# PlusCartUnified_X7.net
KiCad netlist of a schematic drawn in EAGLE
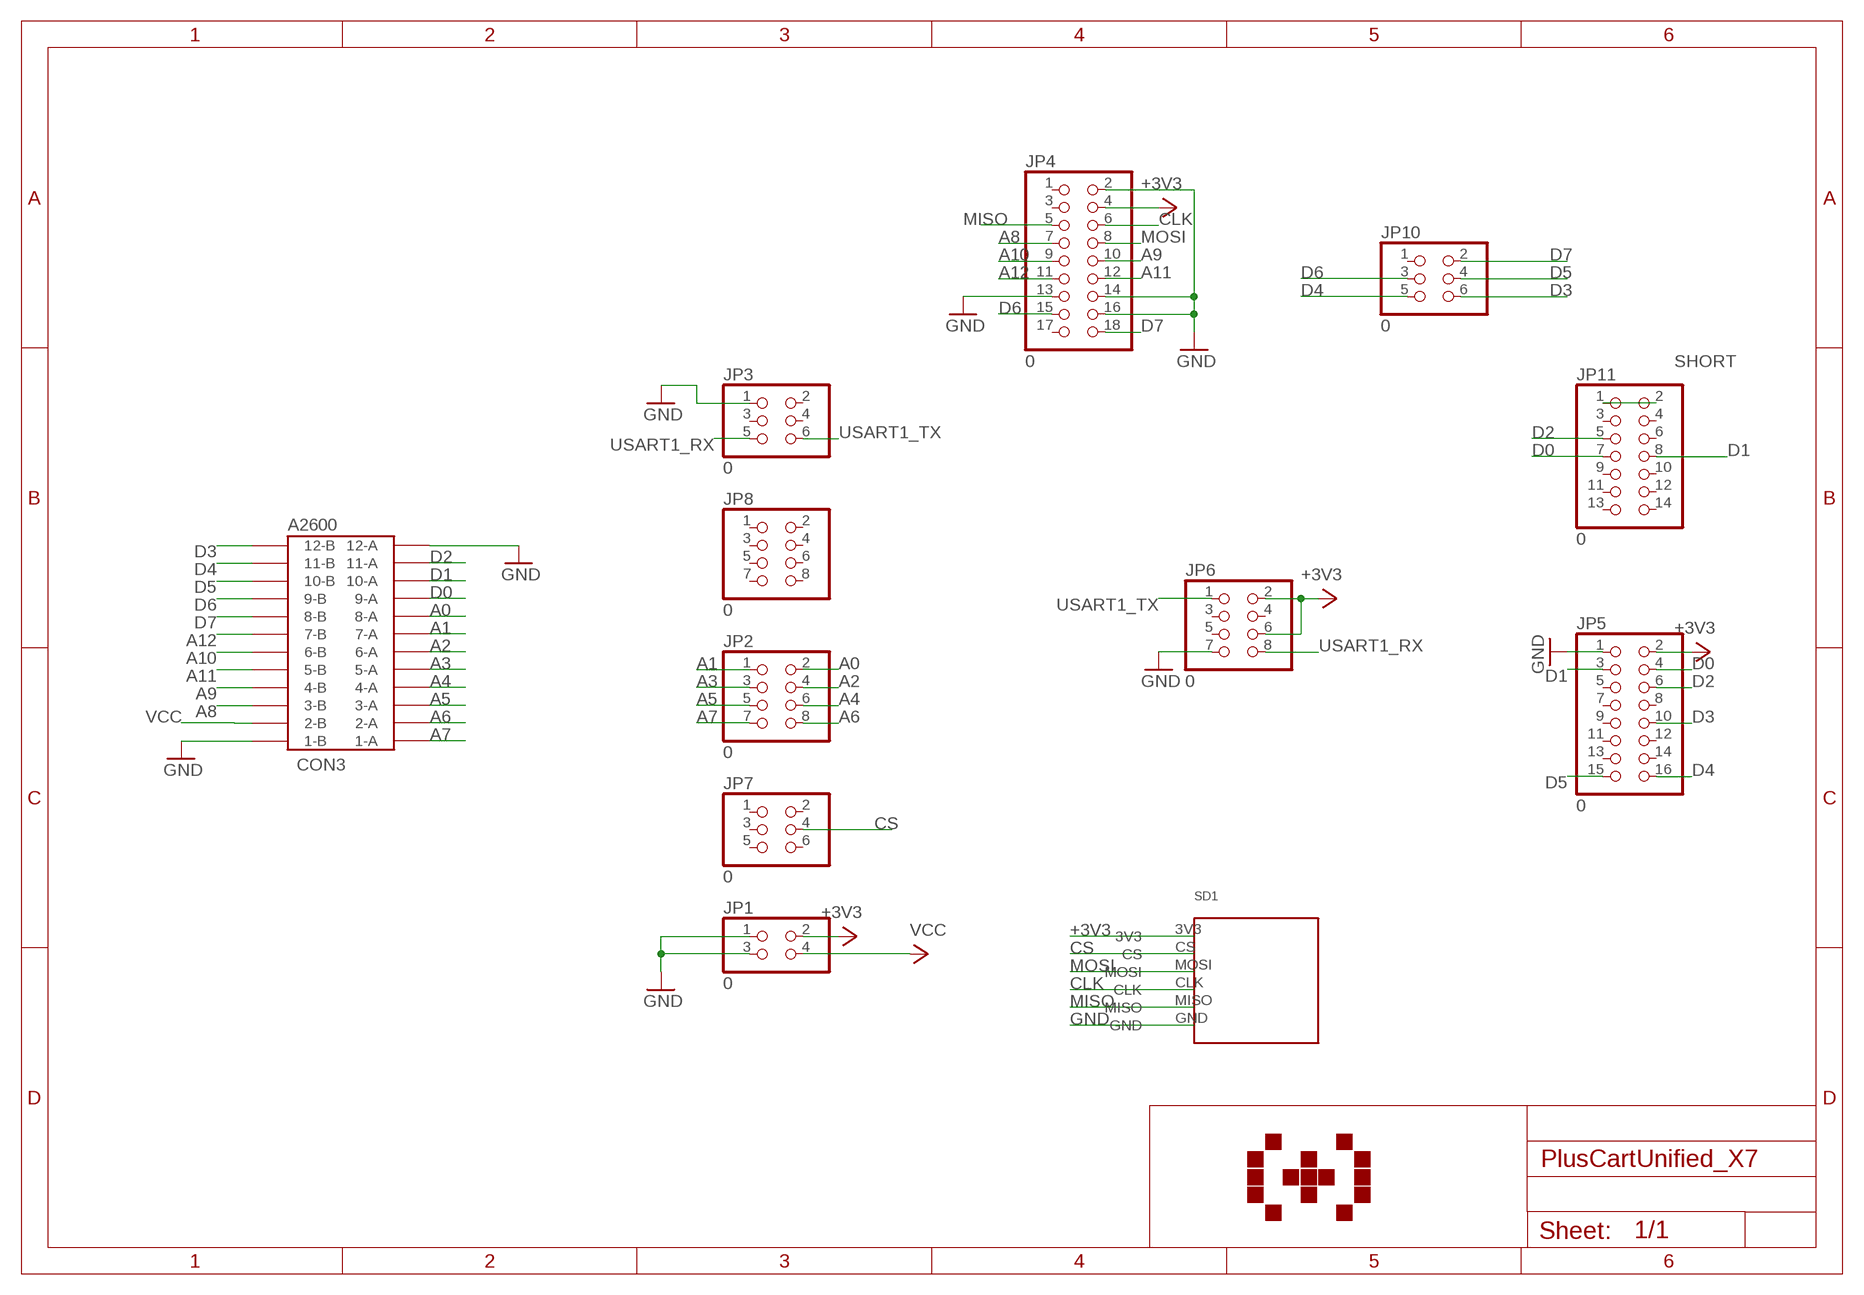
[diagram p0: schematic, sheet 1]

(export (version "E")
  (design (tool "Eeschema 10.0.6"))
  (components
    (comp (ref "CON3")
      (value "A2600")
      (footprint "eagle-import:24PINEDGE-254MM")
      (libsource (lib "eagle-import") (part "24PINEDGE-254MM"))
    )
    (comp (ref "JP1")
      (value "0")
      (footprint "eagle-import:2X02")
      (libsource (lib "eagle-import") (part "PINHD-2X2"))
    )
    (comp (ref "JP2")
      (value "0")
      (footprint "eagle-import:2X04")
      (libsource (lib "eagle-import") (part "PINHD-2X4"))
    )
    (comp (ref "JP3")
      (value "0")
      (footprint "eagle-import:2X03")
      (libsource (lib "eagle-import") (part "PINHD-2X3"))
    )
    (comp (ref "JP4")
      (value "0")
      (footprint "eagle-import:2X09")
      (libsource (lib "eagle-import") (part "PINHD-2X9"))
    )
    (comp (ref "JP5")
      (value "0")
      (footprint "eagle-import:2X08")
      (libsource (lib "eagle-import") (part "PINHD-2X8"))
    )
    (comp (ref "JP6")
      (value "0")
      (footprint "eagle-import:2X04")
      (libsource (lib "eagle-import") (part "PINHD-2X4"))
    )
    (comp (ref "JP7")
      (value "0")
      (footprint "eagle-import:2X03")
      (libsource (lib "eagle-import") (part "pinhead@1_PINHD-2X3"))
    )
    (comp (ref "JP8")
      (value "0")
      (footprint "eagle-import:2X04")
      (libsource (lib "eagle-import") (part "pinhead@1_PINHD-2X4"))
    )
    (comp (ref "JP10")
      (value "0")
      (footprint "eagle-import:2X03")
      (libsource (lib "eagle-import") (part "pinhead@1_PINHD-2X3"))
    )
    (comp (ref "JP11")
      (value "0")
      (footprint "eagle-import:2X07")
      (libsource (lib "eagle-import") (part "PINHD-2X7"))
    )
    (comp (ref "SD1")
      (value "MICROSDMICROSD2")
      (footprint "eagle-import:MICROSD_FOOTPRINT")
      (libsource (lib "eagle-import") (part "MICROSDMICROSD2"))
    )
  )
  (nets
    (net (code "1") (name "+3V3") (class "Default")
      (node (ref "JP1") (pin "2") (pinfunction "2_2") (pintype "passive"))
      (node (ref "JP4") (pin "4") (pinfunction "4_4") (pintype "passive"))
      (node (ref "JP5") (pin "2") (pinfunction "2_2") (pintype "passive"))
      (node (ref "JP6") (pin "2") (pinfunction "2_2") (pintype "passive"))
      (node (ref "JP6") (pin "6") (pinfunction "6_6") (pintype "passive"))
      (node (ref "SD1") (pin "3V3") (pinfunction "3V3_3V3") (pintype "bidirectional"))
    )
    (net (code "2") (name "/A0") (class "Default")
      (node (ref "CON3") (pin "8-A") (pinfunction "8-A_8-A") (pintype "passive"))
      (node (ref "JP2") (pin "2") (pinfunction "2_2") (pintype "passive"))
    )
    (net (code "3") (name "/A1") (class "Default")
      (node (ref "CON3") (pin "7-A") (pinfunction "7-A_7-A") (pintype "passive"))
      (node (ref "JP2") (pin "1") (pinfunction "1_1") (pintype "passive"))
    )
    (net (code "4") (name "/A2") (class "Default")
      (node (ref "CON3") (pin "6-A") (pinfunction "6-A_6-A") (pintype "passive"))
      (node (ref "JP2") (pin "4") (pinfunction "4_4") (pintype "passive"))
    )
    (net (code "5") (name "/A3") (class "Default")
      (node (ref "CON3") (pin "5-A") (pinfunction "5-A_5-A") (pintype "passive"))
      (node (ref "JP2") (pin "3") (pinfunction "3_3") (pintype "passive"))
    )
    (net (code "6") (name "/A4") (class "Default")
      (node (ref "CON3") (pin "4-A") (pinfunction "4-A_4-A") (pintype "passive"))
      (node (ref "JP2") (pin "6") (pinfunction "6_6") (pintype "passive"))
    )
    (net (code "7") (name "/A5") (class "Default")
      (node (ref "CON3") (pin "3-A") (pinfunction "3-A_3-A") (pintype "passive"))
      (node (ref "JP2") (pin "5") (pinfunction "5_5") (pintype "passive"))
    )
    (net (code "8") (name "/A6") (class "Default")
      (node (ref "CON3") (pin "2-A") (pinfunction "2-A_2-A") (pintype "passive"))
      (node (ref "JP2") (pin "8") (pinfunction "8_8") (pintype "passive"))
    )
    (net (code "9") (name "/A7") (class "Default")
      (node (ref "CON3") (pin "1-A") (pinfunction "1-A_1-A") (pintype "passive"))
      (node (ref "JP2") (pin "7") (pinfunction "7_7") (pintype "passive"))
    )
    (net (code "10") (name "/A8") (class "Default")
      (node (ref "CON3") (pin "3-B") (pinfunction "3-B_3-B") (pintype "passive"))
      (node (ref "JP4") (pin "7") (pinfunction "7_7") (pintype "passive"))
    )
    (net (code "11") (name "/A9") (class "Default")
      (node (ref "CON3") (pin "4-B") (pinfunction "4-B_4-B") (pintype "passive"))
      (node (ref "JP4") (pin "10") (pinfunction "10_10") (pintype "passive"))
    )
    (net (code "12") (name "/A10") (class "Default")
      (node (ref "CON3") (pin "6-B") (pinfunction "6-B_6-B") (pintype "passive"))
      (node (ref "JP4") (pin "9") (pinfunction "9_9") (pintype "passive"))
    )
    (net (code "13") (name "/A11") (class "Default")
      (node (ref "CON3") (pin "5-B") (pinfunction "5-B_5-B") (pintype "passive"))
      (node (ref "JP4") (pin "12") (pinfunction "12_12") (pintype "passive"))
    )
    (net (code "14") (name "/A12") (class "Default")
      (node (ref "CON3") (pin "7-B") (pinfunction "7-B_7-B") (pintype "passive"))
      (node (ref "JP4") (pin "11") (pinfunction "11_11") (pintype "passive"))
    )
    (net (code "15") (name "/CLK") (class "Default")
      (node (ref "JP4") (pin "6") (pinfunction "6_6") (pintype "passive"))
      (node (ref "SD1") (pin "CLK") (pinfunction "CLK_CLK") (pintype "bidirectional"))
    )
    (net (code "16") (name "/CS") (class "Default")
      (node (ref "JP7") (pin "4") (pinfunction "4_4") (pintype "passive"))
      (node (ref "SD1") (pin "CS") (pinfunction "CS_CS") (pintype "bidirectional"))
    )
    (net (code "17") (name "/D0") (class "Default")
      (node (ref "CON3") (pin "9-A") (pinfunction "9-A_9-A") (pintype "passive"))
      (node (ref "JP11") (pin "7") (pinfunction "7_7") (pintype "passive"))
      (node (ref "JP5") (pin "4") (pinfunction "4_4") (pintype "passive"))
    )
    (net (code "18") (name "/D1") (class "Default")
      (node (ref "CON3") (pin "10-A") (pinfunction "10-A_10-A") (pintype "passive"))
      (node (ref "JP11") (pin "8") (pinfunction "8_8") (pintype "passive"))
      (node (ref "JP5") (pin "3") (pinfunction "3_3") (pintype "passive"))
    )
    (net (code "19") (name "/D2") (class "Default")
      (node (ref "CON3") (pin "11-A") (pinfunction "11-A_11-A") (pintype "passive"))
      (node (ref "JP11") (pin "5") (pinfunction "5_5") (pintype "passive"))
      (node (ref "JP5") (pin "6") (pinfunction "6_6") (pintype "passive"))
    )
    (net (code "20") (name "/D3") (class "Default")
      (node (ref "CON3") (pin "12-B") (pinfunction "12-B_12-B") (pintype "passive"))
      (node (ref "JP10") (pin "6") (pinfunction "6_6") (pintype "passive"))
      (node (ref "JP5") (pin "10") (pinfunction "10_10") (pintype "passive"))
    )
    (net (code "21") (name "/D4") (class "Default")
      (node (ref "CON3") (pin "11-B") (pinfunction "11-B_11-B") (pintype "passive"))
      (node (ref "JP10") (pin "5") (pinfunction "5_5") (pintype "passive"))
      (node (ref "JP5") (pin "16") (pinfunction "16_16") (pintype "passive"))
    )
    (net (code "22") (name "/D5") (class "Default")
      (node (ref "CON3") (pin "10-B") (pinfunction "10-B_10-B") (pintype "passive"))
      (node (ref "JP10") (pin "4") (pinfunction "4_4") (pintype "passive"))
      (node (ref "JP5") (pin "15") (pinfunction "15_15") (pintype "passive"))
    )
    (net (code "23") (name "/D6") (class "Default")
      (node (ref "CON3") (pin "9-B") (pinfunction "9-B_9-B") (pintype "passive"))
      (node (ref "JP10") (pin "3") (pinfunction "3_3") (pintype "passive"))
      (node (ref "JP4") (pin "15") (pinfunction "15_15") (pintype "passive"))
    )
    (net (code "24") (name "/D7") (class "Default")
      (node (ref "CON3") (pin "8-B") (pinfunction "8-B_8-B") (pintype "passive"))
      (node (ref "JP10") (pin "2") (pinfunction "2_2") (pintype "passive"))
      (node (ref "JP4") (pin "18") (pinfunction "18_18") (pintype "passive"))
    )
    (net (code "25") (name "/MISO") (class "Default")
      (node (ref "JP4") (pin "5") (pinfunction "5_5") (pintype "passive"))
      (node (ref "SD1") (pin "MISO") (pinfunction "MISO_MISO") (pintype "bidirectional"))
    )
    (net (code "26") (name "/MOSI") (class "Default")
      (node (ref "JP4") (pin "8") (pinfunction "8_8") (pintype "passive"))
      (node (ref "SD1") (pin "MOSI") (pinfunction "MOSI_MOSI") (pintype "bidirectional"))
    )
    (net (code "27") (name "/SHORT") (class "Default")
      (node (ref "JP11") (pin "1") (pinfunction "1_1") (pintype "passive"))
      (node (ref "JP11") (pin "2") (pinfunction "2_2") (pintype "passive"))
    )
    (net (code "28") (name "/USART1_RX") (class "Default")
      (node (ref "JP3") (pin "5") (pinfunction "5_5") (pintype "passive"))
      (node (ref "JP6") (pin "8") (pinfunction "8_8") (pintype "passive"))
    )
    (net (code "29") (name "/USART1_TX") (class "Default")
      (node (ref "JP3") (pin "6") (pinfunction "6_6") (pintype "passive"))
      (node (ref "JP6") (pin "1") (pinfunction "1_1") (pintype "passive"))
    )
    (net (code "30") (name "GND") (class "Default")
      (node (ref "CON3") (pin "1-B") (pinfunction "1-B_1-B") (pintype "passive"))
      (node (ref "CON3") (pin "12-A") (pinfunction "12-A_12-A") (pintype "passive"))
      (node (ref "JP1") (pin "1") (pinfunction "1_1") (pintype "passive"))
      (node (ref "JP1") (pin "3") (pinfunction "3_3") (pintype "passive"))
      (node (ref "JP3") (pin "1") (pinfunction "1_1") (pintype "passive"))
      (node (ref "JP4") (pin "13") (pinfunction "13_13") (pintype "passive"))
      (node (ref "JP4") (pin "14") (pinfunction "14_14") (pintype "passive"))
      (node (ref "JP4") (pin "16") (pinfunction "16_16") (pintype "passive"))
      (node (ref "JP4") (pin "2") (pinfunction "2_2") (pintype "passive"))
      (node (ref "JP5") (pin "1") (pinfunction "1_1") (pintype "passive"))
      (node (ref "JP6") (pin "7") (pinfunction "7_7") (pintype "passive"))
      (node (ref "SD1") (pin "GND") (pinfunction "GND_GND") (pintype "bidirectional"))
    )
    (net (code "31") (name "VCC") (class "Default")
      (node (ref "CON3") (pin "2-B") (pinfunction "2-B_2-B") (pintype "passive"))
      (node (ref "JP1") (pin "4") (pinfunction "4_4") (pintype "passive"))
    )
    (net (code "32") (name "unconnected-(JP3-Pad2)") (class "Default")
      (node (ref "JP3") (pin "2") (pinfunction "2_2") (pintype "passive"))
    )
    (net (code "33") (name "unconnected-(JP3-Pad3)") (class "Default")
      (node (ref "JP3") (pin "3") (pinfunction "3_3") (pintype "passive"))
    )
    (net (code "34") (name "unconnected-(JP3-Pad4)") (class "Default")
      (node (ref "JP3") (pin "4") (pinfunction "4_4") (pintype "passive"))
    )
    (net (code "35") (name "unconnected-(JP4-Pad1)") (class "Default")
      (node (ref "JP4") (pin "1") (pinfunction "1_1") (pintype "passive"))
    )
    (net (code "36") (name "unconnected-(JP4-Pad3)") (class "Default")
      (node (ref "JP4") (pin "3") (pinfunction "3_3") (pintype "passive"))
    )
    (net (code "37") (name "unconnected-(JP4-Pad17)") (class "Default")
      (node (ref "JP4") (pin "17") (pinfunction "17_17") (pintype "passive"))
    )
    (net (code "38") (name "unconnected-(JP5-Pad5)") (class "Default")
      (node (ref "JP5") (pin "5") (pinfunction "5_5") (pintype "passive"))
    )
    (net (code "39") (name "unconnected-(JP5-Pad7)") (class "Default")
      (node (ref "JP5") (pin "7") (pinfunction "7_7") (pintype "passive"))
    )
    (net (code "40") (name "unconnected-(JP5-Pad8)") (class "Default")
      (node (ref "JP5") (pin "8") (pinfunction "8_8") (pintype "passive"))
    )
    (net (code "41") (name "unconnected-(JP5-Pad9)") (class "Default")
      (node (ref "JP5") (pin "9") (pinfunction "9_9") (pintype "passive"))
    )
    (net (code "42") (name "unconnected-(JP5-Pad11)") (class "Default")
      (node (ref "JP5") (pin "11") (pinfunction "11_11") (pintype "passive"))
    )
    (net (code "43") (name "unconnected-(JP5-Pad12)") (class "Default")
      (node (ref "JP5") (pin "12") (pinfunction "12_12") (pintype "passive"))
    )
    (net (code "44") (name "unconnected-(JP5-Pad13)") (class "Default")
      (node (ref "JP5") (pin "13") (pinfunction "13_13") (pintype "passive"))
    )
    (net (code "45") (name "unconnected-(JP5-Pad14)") (class "Default")
      (node (ref "JP5") (pin "14") (pinfunction "14_14") (pintype "passive"))
    )
    (net (code "46") (name "unconnected-(JP6-Pad3)") (class "Default")
      (node (ref "JP6") (pin "3") (pinfunction "3_3") (pintype "passive"))
    )
    (net (code "47") (name "unconnected-(JP6-Pad4)") (class "Default")
      (node (ref "JP6") (pin "4") (pinfunction "4_4") (pintype "passive"))
    )
    (net (code "48") (name "unconnected-(JP6-Pad5)") (class "Default")
      (node (ref "JP6") (pin "5") (pinfunction "5_5") (pintype "passive"))
    )
    (net (code "49") (name "unconnected-(JP7-Pad1)") (class "Default")
      (node (ref "JP7") (pin "1") (pinfunction "1_1") (pintype "passive"))
    )
    (net (code "50") (name "unconnected-(JP7-Pad2)") (class "Default")
      (node (ref "JP7") (pin "2") (pinfunction "2_2") (pintype "passive"))
    )
    (net (code "51") (name "unconnected-(JP7-Pad3)") (class "Default")
      (node (ref "JP7") (pin "3") (pinfunction "3_3") (pintype "passive"))
    )
    (net (code "52") (name "unconnected-(JP7-Pad5)") (class "Default")
      (node (ref "JP7") (pin "5") (pinfunction "5_5") (pintype "passive"))
    )
    (net (code "53") (name "unconnected-(JP7-Pad6)") (class "Default")
      (node (ref "JP7") (pin "6") (pinfunction "6_6") (pintype "passive"))
    )
    (net (code "54") (name "unconnected-(JP8-Pad1)") (class "Default")
      (node (ref "JP8") (pin "1") (pinfunction "1_1") (pintype "passive"))
    )
    (net (code "55") (name "unconnected-(JP8-Pad2)") (class "Default")
      (node (ref "JP8") (pin "2") (pinfunction "2_2") (pintype "passive"))
    )
    (net (code "56") (name "unconnected-(JP8-Pad3)") (class "Default")
      (node (ref "JP8") (pin "3") (pinfunction "3_3") (pintype "passive"))
    )
    (net (code "57") (name "unconnected-(JP8-Pad4)") (class "Default")
      (node (ref "JP8") (pin "4") (pinfunction "4_4") (pintype "passive"))
    )
    (net (code "58") (name "unconnected-(JP8-Pad5)") (class "Default")
      (node (ref "JP8") (pin "5") (pinfunction "5_5") (pintype "passive"))
    )
    (net (code "59") (name "unconnected-(JP8-Pad6)") (class "Default")
      (node (ref "JP8") (pin "6") (pinfunction "6_6") (pintype "passive"))
    )
    (net (code "60") (name "unconnected-(JP8-Pad7)") (class "Default")
      (node (ref "JP8") (pin "7") (pinfunction "7_7") (pintype "passive"))
    )
    (net (code "61") (name "unconnected-(JP8-Pad8)") (class "Default")
      (node (ref "JP8") (pin "8") (pinfunction "8_8") (pintype "passive"))
    )
    (net (code "62") (name "unconnected-(JP10-Pad1)") (class "Default")
      (node (ref "JP10") (pin "1") (pinfunction "1_1") (pintype "passive"))
    )
    (net (code "63") (name "unconnected-(JP11-Pad3)") (class "Default")
      (node (ref "JP11") (pin "3") (pinfunction "3_3") (pintype "passive"))
    )
    (net (code "64") (name "unconnected-(JP11-Pad4)") (class "Default")
      (node (ref "JP11") (pin "4") (pinfunction "4_4") (pintype "passive"))
    )
    (net (code "65") (name "unconnected-(JP11-Pad6)") (class "Default")
      (node (ref "JP11") (pin "6") (pinfunction "6_6") (pintype "passive"))
    )
    (net (code "66") (name "unconnected-(JP11-Pad9)") (class "Default")
      (node (ref "JP11") (pin "9") (pinfunction "9_9") (pintype "passive"))
    )
    (net (code "67") (name "unconnected-(JP11-Pad10)") (class "Default")
      (node (ref "JP11") (pin "10") (pinfunction "10_10") (pintype "passive"))
    )
    (net (code "68") (name "unconnected-(JP11-Pad11)") (class "Default")
      (node (ref "JP11") (pin "11") (pinfunction "11_11") (pintype "passive"))
    )
    (net (code "69") (name "unconnected-(JP11-Pad12)") (class "Default")
      (node (ref "JP11") (pin "12") (pinfunction "12_12") (pintype "passive"))
    )
    (net (code "70") (name "unconnected-(JP11-Pad13)") (class "Default")
      (node (ref "JP11") (pin "13") (pinfunction "13_13") (pintype "passive"))
    )
    (net (code "71") (name "unconnected-(JP11-Pad14)") (class "Default")
      (node (ref "JP11") (pin "14") (pinfunction "14_14") (pintype "passive"))
    )
  )
)
